# PCBMINI.net
KiCad netlist of a schematic drawn in EAGLE
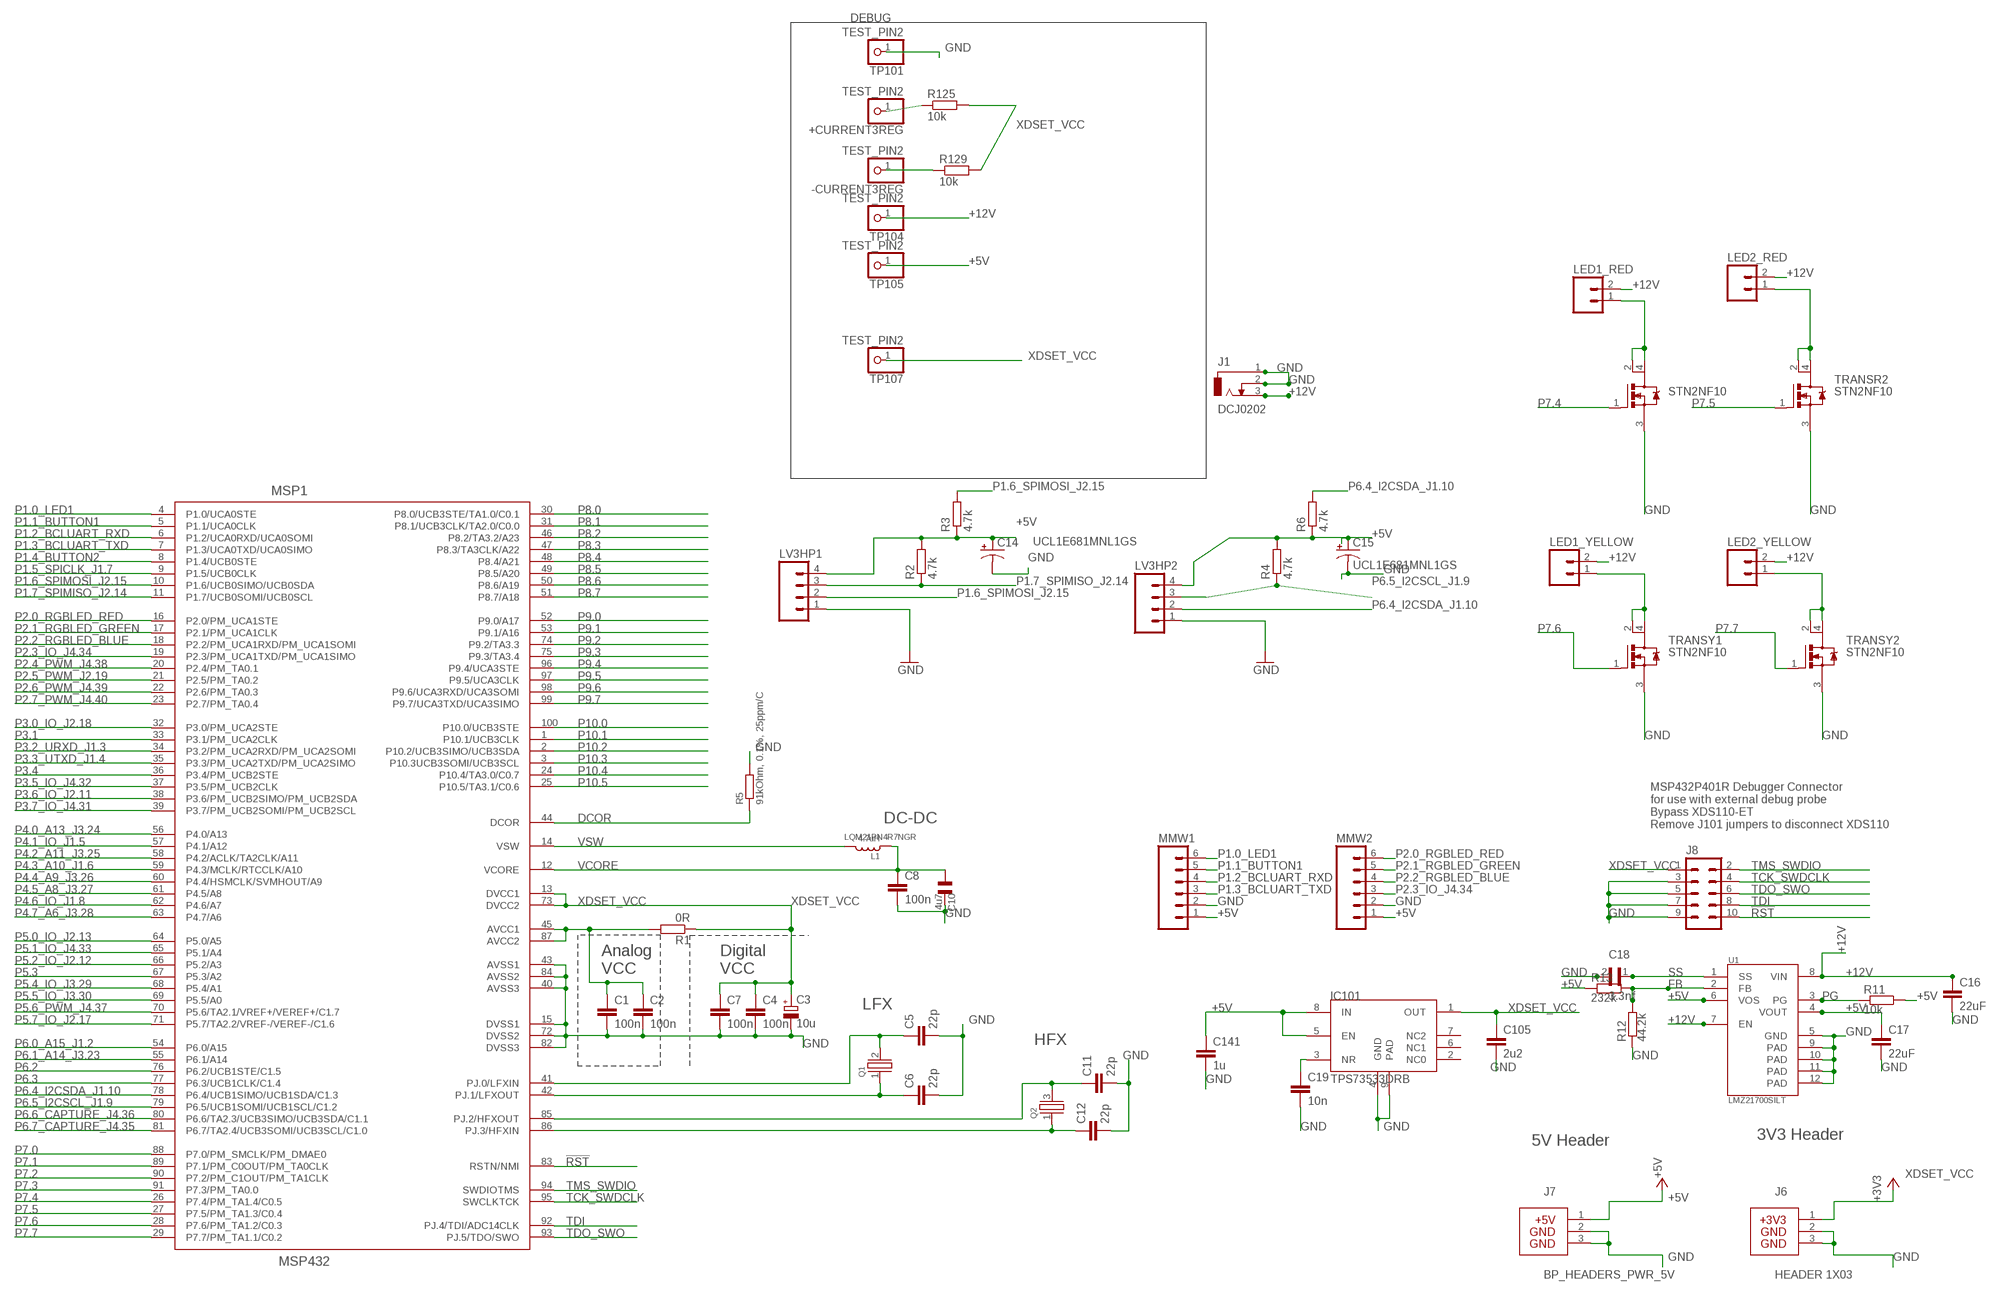
[diagram p0: schematic, sheet 1, part 1 of 2]
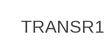
[diagram p1: schematic, sheet 1, part 2 of 2]

(export (version "E")
  (design (tool "Eeschema 10.0.6"))
  (components
    (comp (ref "+CURRENT3REG")
      (value "TEST_PIN2")
      (footprint "eagle-import:1X01")
      (libsource (lib "eagle-import") (part "PINHD-1X1"))
    )
    (comp (ref "-CURRENT3REG")
      (value "TEST_PIN2")
      (footprint "eagle-import:1X01")
      (libsource (lib "eagle-import") (part "PINHD-1X1"))
    )
    (comp (ref "C1")
      (value "100n")
      (footprint "eagle-import:0402")
      (libsource (lib "eagle-import") (part "C-EUCM0402"))
    )
    (comp (ref "C2")
      (value "100n")
      (footprint "eagle-import:0402")
      (libsource (lib "eagle-import") (part "C-EUCM0402"))
    )
    (comp (ref "C3")
      (value "10u")
      (footprint "eagle-import:A_3216-18R")
      (libsource (lib "eagle-import") (part "CPOL-EUA/3216-18R"))
    )
    (comp (ref "C4")
      (value "100n")
      (footprint "eagle-import:0402")
      (libsource (lib "eagle-import") (part "C-EUCM0402"))
    )
    (comp (ref "C5")
      (value "22p")
      (footprint "eagle-import:0402")
      (libsource (lib "eagle-import") (part "C-EUCM0402"))
    )
    (comp (ref "C6")
      (value "22p")
      (footprint "eagle-import:0402")
      (libsource (lib "eagle-import") (part "C-EUCM0402"))
    )
    (comp (ref "C7")
      (value "100n")
      (footprint "eagle-import:0402")
      (libsource (lib "eagle-import") (part "C-EUCM0402"))
    )
    (comp (ref "C8")
      (value "100n")
      (footprint "eagle-import:0402")
      (libsource (lib "eagle-import") (part "C-EUCM0402"))
    )
    (comp (ref "C10")
      (value "4u7")
      (footprint "eagle-import:CSMD0805")
      (libsource (lib "eagle-import") (part "CSMD0805"))
    )
    (comp (ref "C11")
      (value "22p")
      (footprint "eagle-import:0402")
      (libsource (lib "eagle-import") (part "C-EUCM0402"))
    )
    (comp (ref "C12")
      (value "22p")
      (footprint "eagle-import:0402")
      (libsource (lib "eagle-import") (part "C-EUCM0402"))
    )
    (comp (ref "C14")
      (value "UCL1E681MNL1GS")
      (footprint "eagle-import:CAPAE1030X1350N")
      (fields (field (name "MF") "Nichicon"))
      (libsource (lib "eagle-import") (part "UCL1E681MNL1GS"))
    )
    (comp (ref "C15")
      (value "UCL1E681MNL1GS")
      (footprint "eagle-import:CAPAE1030X1350N")
      (fields (field (name "MF") "Nichicon"))
      (libsource (lib "eagle-import") (part "UCL1E681MNL1GS"))
    )
    (comp (ref "C16")
      (value "22uF")
      (footprint "eagle-import:0805")
      (libsource (lib "eagle-import") (part "22UF-0805-6.3V-20%"))
    )
    (comp (ref "C17")
      (value "22uF")
      (footprint "eagle-import:0805")
      (libsource (lib "eagle-import") (part "22UF-0805-6.3V-20%"))
    )
    (comp (ref "C18")
      (value "3.3nf")
      (footprint "eagle-import:CAPC1005X55N")
      (fields (field (name "MF") "KEMET") (field (name "MP") "C0402C332K5RACTU"))
      (libsource (lib "eagle-import") (part "C0402C332K5RACTU"))
    )
    (comp (ref "C19")
      (value "10n")
      (footprint "eagle-import:C0603")
      (libsource (lib "eagle-import") (part "C-EUC0603"))
    )
    (comp (ref "C105")
      (value "2u2")
      (footprint "eagle-import:C0603")
      (libsource (lib "eagle-import") (part "C-EUC0603"))
    )
    (comp (ref "C141")
      (value "1u")
      (footprint "eagle-import:C0603")
      (libsource (lib "eagle-import") (part "C-EUC0603"))
    )
    (comp (ref "IC101")
      (value "TPS73533DRB")
      (footprint "eagle-import:SON8")
      (libsource (lib "eagle-import") (part "TPS73633DRB"))
    )
    (comp (ref "J1")
      (value "DCJ0202")
      (footprint "eagle-import:DCJ0202")
      (libsource (lib "eagle-import") (part "DCJ0202"))
    )
    (comp (ref "J6")
      (value "HEADER 1X03")
      (footprint "eagle-import:3PIN_PWR_3V3")
      (libsource (lib "eagle-import") (part "BP_HEADERS_PWR_3V3-TH100"))
    )
    (comp (ref "J7")
      (value "BP_HEADERS_PWR_5V")
      (footprint "eagle-import:3PIN_PWR_5V")
      (libsource (lib "eagle-import") (part "BP_HEADERS_PWR_5V"))
    )
    (comp (ref "J8")
      (value "DEBUG_ARM-10")
      (footprint "eagle-import:ARM-10")
      (libsource (lib "eagle-import") (part "DEBUG_ARM-10"))
    )
    (comp (ref "L1")
      (value "4.7uH")
      (footprint "eagle-import:0806")
      (libsource (lib "eagle-import") (part "LQM2MP_G0"))
    )
    (comp (ref "LED1_RED")
      (value "MA02")
      (footprint "eagle-import:02PA")
      (libsource (lib "eagle-import") (part "MA02"))
    )
    (comp (ref "LED1_YELLOW")
      (value "MA02")
      (footprint "eagle-import:02PA")
      (libsource (lib "eagle-import") (part "MA02"))
    )
    (comp (ref "LED2_RED")
      (value "MA02")
      (footprint "eagle-import:02PA")
      (libsource (lib "eagle-import") (part "MA02"))
    )
    (comp (ref "LED2_YELLOW")
      (value "MA02")
      (footprint "eagle-import:02PA")
      (libsource (lib "eagle-import") (part "MA02"))
    )
    (comp (ref "LV3HP1")
      (value "MA04")
      (footprint "eagle-import:04PA")
      (libsource (lib "eagle-import") (part "MA04"))
    )
    (comp (ref "LV3HP2")
      (value "MA04")
      (footprint "eagle-import:04PA")
      (libsource (lib "eagle-import") (part "MA04"))
    )
    (comp (ref "MMW1")
      (value "MA06")
      (footprint "eagle-import:06PA")
      (libsource (lib "eagle-import") (part "MA06"))
    )
    (comp (ref "MMW2")
      (value "MA06")
      (footprint "eagle-import:06PA")
      (libsource (lib "eagle-import") (part "MA06"))
    )
    (comp (ref "MSP1")
      (value "MSP432")
      (footprint "eagle-import:PZ100")
      (libsource (lib "eagle-import") (part "MSP432"))
    )
    (comp (ref "Q1")
      (value "CRYSTALLF_GENERAL")
      (footprint "eagle-import:LF_XTAL")
      (libsource (lib "eagle-import") (part "CRYSTALLF_GENERAL"))
    )
    (comp (ref "Q2")
      (value "CRYSTALEPSON_FA-238")
      (footprint "eagle-import:FA-238")
      (libsource (lib "eagle-import") (part "CRYSTALEPSON_FA-238"))
    )
    (comp (ref "R1")
      (value "0R")
      (footprint "eagle-import:0402")
      (libsource (lib "eagle-import") (part "R-EU_RM0402"))
    )
    (comp (ref "R2")
      (value "4.7k")
      (footprint "eagle-import:0402")
      (libsource (lib "eagle-import") (part "R-EU_RM0402"))
    )
    (comp (ref "R3")
      (value "4.7k")
      (footprint "eagle-import:0402")
      (libsource (lib "eagle-import") (part "R-EU_RM0402"))
    )
    (comp (ref "R4")
      (value "4.7k")
      (footprint "eagle-import:0402")
      (libsource (lib "eagle-import") (part "R-EU_RM0402"))
    )
    (comp (ref "R5")
      (value "91kOhm, 0.1%, 25ppm/C")
      (footprint "eagle-import:0805")
      (libsource (lib "eagle-import") (part "R_0805"))
    )
    (comp (ref "R6")
      (value "4.7k")
      (footprint "eagle-import:0402")
      (libsource (lib "eagle-import") (part "R-EU_RM0402"))
    )
    (comp (ref "R11")
      (value "10k")
      (footprint "eagle-import:SMK")
      (libsource (lib "eagle-import") (part "SMK"))
    )
    (comp (ref "R12")
      (value "44.2k")
      (footprint "eagle-import:SMK")
      (libsource (lib "eagle-import") (part "SMK"))
    )
    (comp (ref "R13")
      (value "232k")
      (footprint "eagle-import:SMK")
      (libsource (lib "eagle-import") (part "SMK"))
    )
    (comp (ref "R125")
      (value "10k")
      (footprint "eagle-import:0402")
      (libsource (lib "eagle-import") (part "R-EU_RM0402"))
    )
    (comp (ref "R129")
      (value "10k")
      (footprint "eagle-import:0402")
      (libsource (lib "eagle-import") (part "R-EU_RM0402"))
    )
    (comp (ref "TP101")
      (value "TEST_PIN2")
      (footprint "eagle-import:1X01")
      (libsource (lib "eagle-import") (part "PINHD-1X1"))
    )
    (comp (ref "TP104")
      (value "TEST_PIN2")
      (footprint "eagle-import:1X01")
      (libsource (lib "eagle-import") (part "PINHD-1X1"))
    )
    (comp (ref "TP105")
      (value "TEST_PIN2")
      (footprint "eagle-import:1X01")
      (libsource (lib "eagle-import") (part "PINHD-1X1"))
    )
    (comp (ref "TP107")
      (value "TEST_PIN2")
      (footprint "eagle-import:1X01")
      (libsource (lib "eagle-import") (part "PINHD-1X1"))
    )
    (comp (ref "TRANSR1")
      (value "STN2NF10")
      (footprint "eagle-import:SOT230P700X180-4N")
      (fields (field (name "MF") "STMicroelectronics"))
      (libsource (lib "eagle-import") (part "STN2NF10"))
    )
    (comp (ref "TRANSR2")
      (value "STN2NF10")
      (footprint "eagle-import:SOT230P700X180-4N")
      (fields (field (name "MF") "STMicroelectronics"))
      (libsource (lib "eagle-import") (part "STN2NF10"))
    )
    (comp (ref "TRANSY1")
      (value "STN2NF10")
      (footprint "eagle-import:SOT230P700X180-4N")
      (fields (field (name "MF") "STMicroelectronics"))
      (libsource (lib "eagle-import") (part "STN2NF10"))
    )
    (comp (ref "TRANSY2")
      (value "STN2NF10")
      (footprint "eagle-import:SOT230P700X180-4N")
      (fields (field (name "MF") "STMicroelectronics"))
      (libsource (lib "eagle-import") (part "STN2NF10"))
    )
    (comp (ref "U1")
      (value "LMZ21700SILT")
      (footprint "eagle-import:DFN350X350X175-10RN")
      (fields (field (name "MF") "Texas Instruments"))
      (libsource (lib "eagle-import") (part "LMZ21700SILT"))
    )
  )
  (nets
    (net (code "1") (name "+3V3") (class "Default")
      (node (ref "C105") (pin "1") (pinfunction "1_1") (pintype "passive"))
      (node (ref "C3") (pin "+") (pinfunction "+_+") (pintype "passive"))
      (node (ref "C4") (pin "1") (pinfunction "1_1") (pintype "passive"))
      (node (ref "C7") (pin "1") (pinfunction "1_1") (pintype "passive"))
      (node (ref "IC101") (pin "1") (pinfunction "OUT_1") (pintype "bidirectional"))
      (node (ref "J6") (pin "1") (pinfunction "1_1") (pintype "bidirectional"))
      (node (ref "J8") (pin "1") (pinfunction "1_1") (pintype "passive"))
      (node (ref "MSP1") (pin "13") (pinfunction "DVCC1_13") (pintype "power_in"))
      (node (ref "MSP1") (pin "73") (pinfunction "DVCC2_73") (pintype "power_in"))
      (node (ref "R1") (pin "1") (pinfunction "1_1") (pintype "passive"))
      (node (ref "R125") (pin "2") (pinfunction "2_2") (pintype "passive"))
      (node (ref "R129") (pin "2") (pinfunction "2_2") (pintype "passive"))
      (node (ref "TP107") (pin "1") (pinfunction "1_1") (pintype "passive"))
    )
    (net (code "2") (name "+5V") (class "Default")
      (node (ref "C14") (pin "A") (pinfunction "+_A") (pintype "passive"))
      (node (ref "C141") (pin "1") (pinfunction "1_1") (pintype "passive"))
      (node (ref "C15") (pin "A") (pinfunction "+_A") (pintype "passive"))
      (node (ref "C17") (pin "1") (pinfunction "1_1") (pintype "passive"))
      (node (ref "IC101") (pin "5") (pinfunction "EN_5") (pintype "bidirectional"))
      (node (ref "IC101") (pin "8") (pinfunction "IN_8") (pintype "bidirectional"))
      (node (ref "J7") (pin "1") (pinfunction "1_1") (pintype "bidirectional"))
      (node (ref "LV3HP1") (pin "4") (pinfunction "4_4") (pintype "passive"))
      (node (ref "LV3HP2") (pin "4") (pinfunction "4_4") (pintype "passive"))
      (node (ref "MMW1") (pin "1") (pinfunction "1_1") (pintype "passive"))
      (node (ref "MMW2") (pin "1") (pinfunction "1_1") (pintype "passive"))
      (node (ref "R11") (pin "1") (pinfunction "1_1") (pintype "passive"))
      (node (ref "R13") (pin "2") (pinfunction "2_2") (pintype "passive"))
      (node (ref "R2") (pin "2") (pinfunction "2_2") (pintype "passive"))
      (node (ref "R3") (pin "1") (pinfunction "1_1") (pintype "passive"))
      (node (ref "R4") (pin "2") (pinfunction "2_2") (pintype "passive"))
      (node (ref "R6") (pin "1") (pinfunction "1_1") (pintype "passive"))
      (node (ref "TP105") (pin "1") (pinfunction "1_1") (pintype "passive"))
      (node (ref "U1") (pin "4") (pinfunction "VOUT_4") (pintype "output"))
      (node (ref "U1") (pin "6") (pinfunction "VOS_6") (pintype "input"))
    )
    (net (code "3") (name "/+12V") (class "Default")
      (node (ref "C16") (pin "1") (pinfunction "1_1") (pintype "passive"))
      (node (ref "J1") (pin "3") (pinfunction "3_3") (pintype "passive"))
      (node (ref "LED1_RED") (pin "2") (pinfunction "2_2") (pintype "passive"))
      (node (ref "LED1_YELLOW") (pin "2") (pinfunction "2_2") (pintype "passive"))
      (node (ref "LED2_RED") (pin "2") (pinfunction "2_2") (pintype "passive"))
      (node (ref "LED2_YELLOW") (pin "2") (pinfunction "2_2") (pintype "passive"))
      (node (ref "TP104") (pin "1") (pinfunction "1_1") (pintype "passive"))
      (node (ref "U1") (pin "7") (pinfunction "EN_7") (pintype "input"))
      (node (ref "U1") (pin "8") (pinfunction "VIN_8") (pintype "power_in"))
    )
    (net (code "4") (name "/DCOR") (class "Default")
      (node (ref "MSP1") (pin "44") (pinfunction "DCOR_44") (pintype "power_in"))
      (node (ref "R5") (pin "1") (pinfunction "1_1") (pintype "passive"))
    )
    (net (code "5") (name "/FB") (class "Default")
      (node (ref "R12") (pin "1") (pinfunction "1_1") (pintype "passive"))
      (node (ref "R13") (pin "1") (pinfunction "1_1") (pintype "passive"))
      (node (ref "U1") (pin "2") (pinfunction "FB_2") (pintype "input"))
    )
    (net (code "6") (name "/P1.0_LED1") (class "Default")
      (node (ref "MMW1") (pin "6") (pinfunction "6_6") (pintype "passive"))
      (node (ref "MSP1") (pin "4") (pinfunction "P1.0/UCA0STE_4") (pintype "power_in"))
    )
    (net (code "7") (name "/P1.1_BUTTON1") (class "Default")
      (node (ref "MMW1") (pin "5") (pinfunction "5_5") (pintype "passive"))
      (node (ref "MSP1") (pin "5") (pinfunction "P1.1/UCA0CLK_5") (pintype "power_in"))
    )
    (net (code "8") (name "/P1.2_BCLUART_RXD") (class "Default")
      (node (ref "MMW1") (pin "4") (pinfunction "4_4") (pintype "passive"))
      (node (ref "MSP1") (pin "6") (pinfunction "P1.2/UCA0RXD/UCA0SOMI_6") (pintype "power_in"))
    )
    (net (code "9") (name "/P1.3_BCLUART_TXD") (class "Default")
      (node (ref "MMW1") (pin "3") (pinfunction "3_3") (pintype "passive"))
      (node (ref "MSP1") (pin "7") (pinfunction "P1.3/UCA0TXD/UCA0SIMO_7") (pintype "power_in"))
    )
    (net (code "10") (name "/P1.4_BUTTON2") (class "Default")
      (node (ref "MSP1") (pin "8") (pinfunction "P1.4/UCB0STE_8") (pintype "power_in"))
    )
    (net (code "11") (name "/P1.5_SPICLK_J1.7") (class "Default")
      (node (ref "MSP1") (pin "9") (pinfunction "P1.5/UCB0CLK_9") (pintype "power_in"))
    )
    (net (code "12") (name "/P1.6_SPIMOSI_J2.15") (class "Default")
      (node (ref "LV3HP1") (pin "2") (pinfunction "2_2") (pintype "passive"))
      (node (ref "MSP1") (pin "10") (pinfunction "P1.6/UCB0SIMO/UCB0SDA_10") (pintype "power_in"))
      (node (ref "R3") (pin "2") (pinfunction "2_2") (pintype "passive"))
    )
    (net (code "13") (name "/P1.7_SPIMISO_J2.14") (class "Default")
      (node (ref "LV3HP1") (pin "3") (pinfunction "3_3") (pintype "passive"))
      (node (ref "MSP1") (pin "11") (pinfunction "P1.7/UCB0SOMI/UCB0SCL_11") (pintype "power_in"))
      (node (ref "R2") (pin "1") (pinfunction "1_1") (pintype "passive"))
    )
    (net (code "14") (name "/P2.0_RGBLED_RED") (class "Default")
      (node (ref "MMW2") (pin "6") (pinfunction "6_6") (pintype "passive"))
      (node (ref "MSP1") (pin "16") (pinfunction "P2.0/PM_UCA1STE_16") (pintype "power_in"))
    )
    (net (code "15") (name "/P2.1_RGBLED_GREEN") (class "Default")
      (node (ref "MMW2") (pin "5") (pinfunction "5_5") (pintype "passive"))
      (node (ref "MSP1") (pin "17") (pinfunction "P2.1/PM_UCA1CLK_17") (pintype "power_in"))
    )
    (net (code "16") (name "/P2.2_RGBLED_BLUE") (class "Default")
      (node (ref "MMW2") (pin "4") (pinfunction "4_4") (pintype "passive"))
      (node (ref "MSP1") (pin "18") (pinfunction "P2.2/PM_UCA1RXD/PM_UCA1SOMI_18") (pintype "power_in"))
    )
    (net (code "17") (name "/P2.3_IO_J4.34") (class "Default")
      (node (ref "MMW2") (pin "3") (pinfunction "3_3") (pintype "passive"))
      (node (ref "MSP1") (pin "19") (pinfunction "P2.3/PM_UCA1TXD/PM_UCA1SIMO_19") (pintype "power_in"))
    )
    (net (code "18") (name "/P2.4_PWM_J4.38") (class "Default")
      (node (ref "MSP1") (pin "20") (pinfunction "P2.4/PM_TA0.1_20") (pintype "power_in"))
    )
    (net (code "19") (name "/P2.5_PWM_J2.19") (class "Default")
      (node (ref "MSP1") (pin "21") (pinfunction "P2.5/PM_TA0.2_21") (pintype "power_in"))
    )
    (net (code "20") (name "/P2.6_PWM_J4.39") (class "Default")
      (node (ref "MSP1") (pin "22") (pinfunction "P2.6/PM_TA0.3_22") (pintype "power_in"))
    )
    (net (code "21") (name "/P2.7_PWM_J4.40") (class "Default")
      (node (ref "MSP1") (pin "23") (pinfunction "P2.7/PM_TA0.4_23") (pintype "power_in"))
    )
    (net (code "22") (name "/P3.0_IO_J2.18") (class "Default")
      (node (ref "MSP1") (pin "32") (pinfunction "P3.0/PM_UCA2STE_32") (pintype "power_in"))
    )
    (net (code "23") (name "/P3.1") (class "Default")
      (node (ref "MSP1") (pin "33") (pinfunction "P3.1/PM_UCA2CLK_33") (pintype "power_in"))
    )
    (net (code "24") (name "/P3.2_URXD_J1.3") (class "Default")
      (node (ref "MSP1") (pin "34") (pinfunction "P3.2/PM_UCA2RXD/PM_UCA2SOMI_34") (pintype "power_in"))
    )
    (net (code "25") (name "/P3.3_UTXD_J1.4") (class "Default")
      (node (ref "MSP1") (pin "35") (pinfunction "P3.3/PM_UCA2TXD/PM_UCA2SIMO_35") (pintype "power_in"))
    )
    (net (code "26") (name "/P3.4") (class "Default")
      (node (ref "MSP1") (pin "36") (pinfunction "P3.4/PM_UCB2STE_36") (pintype "power_in"))
    )
    (net (code "27") (name "/P3.5_IO_J4.32") (class "Default")
      (node (ref "MSP1") (pin "37") (pinfunction "P3.5/PM_UCB2CLK_37") (pintype "power_in"))
    )
    (net (code "28") (name "/P3.6_IO_J2.11") (class "Default")
      (node (ref "MSP1") (pin "38") (pinfunction "P3.6/PM_UCB2SIMO/PM_UCB2SDA_38") (pintype "power_in"))
    )
    (net (code "29") (name "/P3.7_IO_J4.31") (class "Default")
      (node (ref "MSP1") (pin "39") (pinfunction "P3.7/PM_UCB2SOMI/PM_UCB2SCL_39") (pintype "power_in"))
    )
    (net (code "30") (name "/P4.0_A13_J3.24") (class "Default")
      (node (ref "MSP1") (pin "56") (pinfunction "P4.0/A13_56") (pintype "power_in"))
    )
    (net (code "31") (name "/P4.1_IO_J1.5") (class "Default")
      (node (ref "MSP1") (pin "57") (pinfunction "P4.1/A12_57") (pintype "power_in"))
    )
    (net (code "32") (name "/P4.2_A11_J3.25") (class "Default")
      (node (ref "MSP1") (pin "58") (pinfunction "P4.2/ACLK/TA2CLK/A11_58") (pintype "power_in"))
    )
    (net (code "33") (name "/P4.3_A10_J1.6") (class "Default")
      (node (ref "MSP1") (pin "59") (pinfunction "P4.3/MCLK/RTCCLK/A10_59") (pintype "power_in"))
    )
    (net (code "34") (name "/P4.4_A9_J3.26") (class "Default")
      (node (ref "MSP1") (pin "60") (pinfunction "P4.4/HSMCLK/SVMHOUT/A9_60") (pintype "power_in"))
    )
    (net (code "35") (name "/P4.5_A8_J3.27") (class "Default")
      (node (ref "MSP1") (pin "61") (pinfunction "P4.5/A8_61") (pintype "power_in"))
    )
    (net (code "36") (name "/P4.6_IO_J1.8") (class "Default")
      (node (ref "MSP1") (pin "62") (pinfunction "P4.6/A7_62") (pintype "power_in"))
    )
    (net (code "37") (name "/P4.7_A6_J3.28") (class "Default")
      (node (ref "MSP1") (pin "63") (pinfunction "P4.7/A6_63") (pintype "power_in"))
    )
    (net (code "38") (name "/P5.0_IO_J2.13") (class "Default")
      (node (ref "MSP1") (pin "64") (pinfunction "P5.0/A5_64") (pintype "power_in"))
    )
    (net (code "39") (name "/P5.1_IO_J4.33") (class "Default")
      (node (ref "MSP1") (pin "65") (pinfunction "P5.1/A4_65") (pintype "power_in"))
    )
    (net (code "40") (name "/P5.2_IO_J2.12") (class "Default")
      (node (ref "MSP1") (pin "66") (pinfunction "P5.2/A3_66") (pintype "power_in"))
    )
    (net (code "41") (name "/P5.3") (class "Default")
      (node (ref "MSP1") (pin "67") (pinfunction "P5.3/A2_67") (pintype "power_in"))
    )
    (net (code "42") (name "/P5.4_IO_J3.29") (class "Default")
      (node (ref "MSP1") (pin "68") (pinfunction "P5.4/A1_68") (pintype "power_in"))
    )
    (net (code "43") (name "/P5.5_IO_J3.30") (class "Default")
      (node (ref "MSP1") (pin "69") (pinfunction "P5.5/A0_69") (pintype "power_in"))
    )
    (net (code "44") (name "/P5.6_PWM_J4.37") (class "Default")
      (node (ref "MSP1") (pin "70") (pinfunction "P5.6/TA2.1/VREF+/VEREF+/C1.7_70") (pintype "power_in"))
    )
    (net (code "45") (name "/P5.7_IO_J2.17") (class "Default")
      (node (ref "MSP1") (pin "71") (pinfunction "P5.7/TA2.2/VREF-/VEREF-/C1.6_71") (pintype "power_in"))
    )
    (net (code "46") (name "/P6.0_A15_J1.2") (class "Default")
      (node (ref "MSP1") (pin "54") (pinfunction "P6.0/A15_54") (pintype "power_in"))
    )
    (net (code "47") (name "/P6.1_A14_J3.23") (class "Default")
      (node (ref "MSP1") (pin "55") (pinfunction "P6.1/A14_55") (pintype "power_in"))
    )
    (net (code "48") (name "/P6.2") (class "Default")
      (node (ref "MSP1") (pin "76") (pinfunction "P6.2/UCB1STE/C1.5_76") (pintype "power_in"))
    )
    (net (code "49") (name "/P6.3") (class "Default")
      (node (ref "MSP1") (pin "77") (pinfunction "P6.3/UCB1CLK/C1.4_77") (pintype "power_in"))
    )
    (net (code "50") (name "/P6.4_I2CSDA_J1.10") (class "Default")
      (node (ref "LV3HP2") (pin "2") (pinfunction "2_2") (pintype "passive"))
      (node (ref "MSP1") (pin "78") (pinfunction "P6.4/UCB1SIMO/UCB1SDA/C1.3_78") (pintype "power_in"))
      (node (ref "R6") (pin "2") (pinfunction "2_2") (pintype "passive"))
    )
    (net (code "51") (name "/P6.5_I2CSCL_J1.9") (class "Default")
      (node (ref "LV3HP2") (pin "3") (pinfunction "3_3") (pintype "passive"))
      (node (ref "MSP1") (pin "79") (pinfunction "P6.5/UCB1SOMI/UCB1SCL/C1.2_79") (pintype "power_in"))
      (node (ref "R4") (pin "1") (pinfunction "1_1") (pintype "passive"))
    )
    (net (code "52") (name "/P6.6_CAPTURE_J4.36") (class "Default")
      (node (ref "MSP1") (pin "80") (pinfunction "P6.6/TA2.3/UCB3SIMO/UCB3SDA/C1.1_80") (pintype "power_in"))
    )
    (net (code "53") (name "/P6.7_CAPTURE_J4.35") (class "Default")
      (node (ref "MSP1") (pin "81") (pinfunction "P6.7/TA2.4/UCB3SOMI/UCB3SCL/C1.0_81") (pintype "power_in"))
    )
    (net (code "54") (name "/P7.0") (class "Default")
      (node (ref "MSP1") (pin "88") (pinfunction "P7.0/PM_SMCLK/PM_DMAE0_88") (pintype "power_in"))
    )
    (net (code "55") (name "/P7.1") (class "Default")
      (node (ref "MSP1") (pin "89") (pinfunction "P7.1/PM_C0OUT/PM_TA0CLK_89") (pintype "power_in"))
    )
    (net (code "56") (name "/P7.2") (class "Default")
      (node (ref "MSP1") (pin "90") (pinfunction "P7.2/PM_C1OUT/PM_TA1CLK_90") (pintype "power_in"))
    )
    (net (code "57") (name "/P7.3") (class "Default")
      (node (ref "MSP1") (pin "91") (pinfunction "P7.3/PM_TA0.0_91") (pintype "power_in"))
    )
    (net (code "58") (name "/P7.4") (class "Default")
      (node (ref "MSP1") (pin "26") (pinfunction "P7.4/PM_TA1.4/C0.5_26") (pintype "power_in"))
      (node (ref "TRANSR1") (pin "1") (pinfunction "G_1") (pintype "passive"))
    )
    (net (code "59") (name "/P7.5") (class "Default")
      (node (ref "MSP1") (pin "27") (pinfunction "P7.5/PM_TA1.3/C0.4_27") (pintype "power_in"))
      (node (ref "TRANSR2") (pin "1") (pinfunction "G_1") (pintype "passive"))
    )
    (net (code "60") (name "/P7.6") (class "Default")
      (node (ref "MSP1") (pin "28") (pinfunction "P7.6/PM_TA1.2/C0.3_28") (pintype "power_in"))
      (node (ref "TRANSY1") (pin "1") (pinfunction "G_1") (pintype "passive"))
    )
    (net (code "61") (name "/P7.7") (class "Default")
      (node (ref "MSP1") (pin "29") (pinfunction "P7.7/PM_TA1.1/C0.2_29") (pintype "power_in"))
      (node (ref "TRANSY2") (pin "1") (pinfunction "G_1") (pintype "passive"))
    )
    (net (code "62") (name "/P8.0") (class "Default")
      (node (ref "MSP1") (pin "30") (pinfunction "P8.0/UCB3STE/TA1.0/C0.1_30") (pintype "power_in"))
    )
    (net (code "63") (name "/P8.1") (class "Default")
      (node (ref "MSP1") (pin "31") (pinfunction "P8.1/UCB3CLK/TA2.0/C0.0_31") (pintype "power_in"))
    )
    (net (code "64") (name "/P8.2") (class "Default")
      (node (ref "MSP1") (pin "46") (pinfunction "P8.2/TA3.2/A23_46") (pintype "power_in"))
    )
    (net (code "65") (name "/P8.3") (class "Default")
      (node (ref "MSP1") (pin "47") (pinfunction "P8.3/TA3CLK/A22_47") (pintype "power_in"))
    )
    (net (code "66") (name "/P8.4") (class "Default")
      (node (ref "MSP1") (pin "48") (pinfunction "P8.4/A21_48") (pintype "power_in"))
    )
    (net (code "67") (name "/P8.5") (class "Default")
      (node (ref "MSP1") (pin "49") (pinfunction "P8.5/A20_49") (pintype "power_in"))
    )
    (net (code "68") (name "/P8.6") (class "Default")
      (node (ref "MSP1") (pin "50") (pinfunction "P8.6/A19_50") (pintype "power_in"))
    )
    (net (code "69") (name "/P8.7") (class "Default")
      (node (ref "MSP1") (pin "51") (pinfunction "P8.7/A18_51") (pintype "power_in"))
    )
    (net (code "70") (name "/P9.0") (class "Default")
      (node (ref "MSP1") (pin "52") (pinfunction "P9.0/A17_52") (pintype "power_in"))
    )
    (net (code "71") (name "/P9.1") (class "Default")
      (node (ref "MSP1") (pin "53") (pinfunction "P9.1/A16_53") (pintype "power_in"))
    )
    (net (code "72") (name "/P9.2") (class "Default")
      (node (ref "MSP1") (pin "74") (pinfunction "P9.2/TA3.3_74") (pintype "power_in"))
    )
    (net (code "73") (name "/P9.3") (class "Default")
      (node (ref "MSP1") (pin "75") (pinfunction "P9.3/TA3.4_75") (pintype "power_in"))
    )
    (net (code "74") (name "/P9.4") (class "Default")
      (node (ref "MSP1") (pin "96") (pinfunction "P9.4/UCA3STE_96") (pintype "power_in"))
    )
    (net (code "75") (name "/P9.5") (class "Default")
      (node (ref "MSP1") (pin "97") (pinfunction "P9.5/UCA3CLK_97") (pintype "power_in"))
    )
    (net (code "76") (name "/P9.6") (class "Default")
      (node (ref "MSP1") (pin "98") (pinfunction "P9.6/UCA3RXD/UCA3SOMI_98") (pintype "power_in"))
    )
    (net (code "77") (name "/P9.7") (class "Default")
      (node (ref "MSP1") (pin "99") (pinfunction "P9.7/UCA3TXD/UCA3SIMO_99") (pintype "power_in"))
    )
    (net (code "78") (name "/P10.0") (class "Default")
      (node (ref "MSP1") (pin "100") (pinfunction "P10.0/UCB3STE_100") (pintype "power_in"))
    )
    (net (code "79") (name "/P10.1") (class "Default")
      (node (ref "MSP1") (pin "1") (pinfunction "P10.1/UCB3CLK_1") (pintype "power_in"))
    )
    (net (code "80") (name "/P10.2") (class "Default")
      (node (ref "MSP1") (pin "2") (pinfunction "P10.2/UCB3SIMO/UCB3SDA_2") (pintype "power_in"))
    )
    (net (code "81") (name "/P10.3") (class "Default")
      (node (ref "MSP1") (pin "3") (pinfunction "P10.3UCB3SOMI/UCB3SCL_3") (pintype "power_in"))
    )
    (net (code "82") (name "/P10.4") (class "Default")
      (node (ref "MSP1") (pin "24") (pinfunction "P10.4/TA3.0/C0.7_24") (pintype "power_in"))
    )
    (net (code "83") (name "/P10.5") (class "Default")
      (node (ref "MSP1") (pin "25") (pinfunction "P10.5/TA3.1/C0.6_25") (pintype "power_in"))
    )
    (net (code "84") (name "/PG") (class "Default")
      (node (ref "R11") (pin "2") (pinfunction "2_2") (pintype "passive"))
      (node (ref "U1") (pin "3") (pinfunction "PG_3") (pintype "output"))
    )
    (net (code "85") (name "/SS") (class "Default")
      (node (ref "C18") (pin "1") (pinfunction "1_1") (pintype "passive"))
      (node (ref "U1") (pin "1") (pinfunction "SS_1") (pintype "input"))
    )
    (net (code "86") (name "/TCK_SWDCLK") (class "Default")
      (node (ref "J8") (pin "4") (pinfunction "4_4") (pintype "passive"))
      (node (ref "MSP1") (pin "95") (pinfunction "SWCLKTCK_95") (pintype "power_in"))
    )
    (net (code "87") (name "/TDI") (class "Default")
      (node (ref "J8") (pin "8") (pinfunction "8_8") (pintype "passive"))
      (node (ref "MSP1") (pin "92") (pinfunction "PJ.4/TDI/ADC14CLK_92") (pintype "power_in"))
    )
    (net (code "88") (name "/TDO_SWO") (class "Default")
      (node (ref "J8") (pin "6") (pinfunction "6_6") (pintype "passive"))
      (node (ref "MSP1") (pin "93") (pinfunction "PJ.5/TDO/SWO_93") (pintype "power_in"))
    )
    (net (code "89") (name "/TMS_SWDIO") (class "Default")
      (node (ref "J8") (pin "2") (pinfunction "2_2") (pintype "passive"))
      (node (ref "MSP1") (pin "94") (pinfunction "SWDIOTMS_94") (pintype "power_in"))
    )
    (net (code "90") (name "/VCORE") (class "Default")
      (node (ref "C10") (pin "1") (pinfunction "1_1") (pintype "passive"))
      (node (ref "C8") (pin "1") (pinfunction "1_1") (pintype "passive"))
      (node (ref "L1") (pin "1") (pinfunction "1_1") (pintype "passive"))
      (node (ref "MSP1") (pin "12") (pinfunction "VCORE_12") (pintype "power_in"))
    )
    (net (code "91") (name "/VSW") (class "Default")
      (node (ref "L1") (pin "2") (pinfunction "2_2") (pintype "passive"))
      (node (ref "MSP1") (pin "14") (pinfunction "VSW_14") (pintype "power_in"))
    )
    (net (code "92") (name "/~{RST}") (class "Default")
      (node (ref "J8") (pin "10") (pinfunction "10_10") (pintype "passive"))
      (node (ref "MSP1") (pin "83") (pinfunction "RSTN/NMI_83") (pintype "power_in"))
    )
    (net (code "93") (name "GND") (class "Default")
      (node (ref "C1") (pin "2") (pinfunction "2_2") (pintype "passive"))
      (node (ref "C10") (pin "2") (pinfunction "2_2") (pintype "passive"))
      (node (ref "C105") (pin "2") (pinfunction "2_2") (pintype "passive"))
      (node (ref "C11") (pin "2") (pinfunction "2_2") (pintype "passive"))
      (node (ref "C12") (pin "2") (pinfunction "2_2") (pintype "passive"))
      (node (ref "C14") (pin "C") (pinfunction "-_C") (pintype "passive"))
      (node (ref "C141") (pin "2") (pinfunction "2_2") (pintype "passive"))
      (node (ref "C15") (pin "C") (pinfunction "-_C") (pintype "passive"))
      (node (ref "C16") (pin "2") (pinfunction "2_2") (pintype "passive"))
      (node (ref "C17") (pin "2") (pinfunction "2_2") (pintype "passive"))
      (node (ref "C18") (pin "2") (pinfunction "2_2") (pintype "passive"))
      (node (ref "C19") (pin "2") (pinfunction "2_2") (pintype "passive"))
      (node (ref "C2") (pin "2") (pinfunction "2_2") (pintype "passive"))
      (node (ref "C3") (pin "-") (pinfunction "-_-") (pintype "passive"))
      (node (ref "C4") (pin "2") (pinfunction "2_2") (pintype "passive"))
      (node (ref "C5") (pin "2") (pinfunction "2_2") (pintype "passive"))
      (node (ref "C6") (pin "2") (pinfunction "2_2") (pintype "passive"))
      (node (ref "C7") (pin "2") (pinfunction "2_2") (pintype "passive"))
      (node (ref "C8") (pin "2") (pinfunction "2_2") (pintype "passive"))
      (node (ref "IC101") (pin "4") (pinfunction "GND_4") (pintype "bidirectional"))
      (node (ref "IC101") (pin "9") (pinfunction "PAD_9") (pintype "bidirectional"))
      (node (ref "J1") (pin "1") (pinfunction "1_1") (pintype "passive"))
      (node (ref "J1") (pin "2") (pinfunction "2_2") (pintype "passive"))
      (node (ref "J6") (pin "2") (pinfunction "2_2") (pintype "bidirectional"))
      (node (ref "J6") (pin "3") (pinfunction "3_3") (pintype "bidirectional"))
      (node (ref "J7") (pin "2") (pinfunction "2_2") (pintype "bidirectional"))
      (node (ref "J7") (pin "3") (pinfunction "3_3") (pintype "bidirectional"))
      (node (ref "J8") (pin "3") (pinfunction "3_3") (pintype "passive"))
      (node (ref "J8") (pin "5") (pinfunction "5_5") (pintype "passive"))
      (node (ref "J8") (pin "7") (pinfunction "7_7") (pintype "passive"))
      (node (ref "J8") (pin "9") (pinfunction "9_9") (pintype "passive"))
      (node (ref "LV3HP1") (pin "1") (pinfunction "1_1") (pintype "passive"))
      (node (ref "LV3HP2") (pin "1") (pinfunction "1_1") (pintype "passive"))
      (node (ref "MMW1") (pin "2") (pinfunction "2_2") (pintype "passive"))
      (node (ref "MMW2") (pin "2") (pinfunction "2_2") (pintype "passive"))
      (node (ref "MSP1") (pin "15") (pinfunction "DVSS1_15") (pintype "power_in"))
      (node (ref "MSP1") (pin "40") (pinfunction "AVSS3_40") (pintype "power_in"))
      (node (ref "MSP1") (pin "43") (pinfunction "AVSS1_43") (pintype "power_in"))
      (node (ref "MSP1") (pin "72") (pinfunction "DVSS2_72") (pintype "power_in"))
      (node (ref "MSP1") (pin "82") (pinfunction "DVSS3_82") (pintype "power_in"))
      (node (ref "MSP1") (pin "84") (pinfunction "AVSS2_84") (pintype "power_in"))
      (node (ref "R12") (pin "2") (pinfunction "2_2") (pintype "passive"))
      (node (ref "R5") (pin "2") (pinfunction "2_2") (pintype "passive"))
      (node (ref "TP101") (pin "1") (pinfunction "1_1") (pintype "passive"))
      (node (ref "TRANSR1") (pin "3") (pinfunction "S_3") (pintype "passive"))
      (node (ref "TRANSR2") (pin "3") (pinfunction "S_3") (pintype "passive"))
      (node (ref "TRANSY1") (pin "3") (pinfunction "S_3") (pintype "passive"))
      (node (ref "TRANSY2") (pin "3") (pinfunction "S_3") (pintype "passive"))
    )
    (net (code "94") (name "Net-(+CURRENT3REG-Pad1)") (class "Default")
      (node (ref "+CURRENT3REG") (pin "1") (pinfunction "1_1") (pintype "passive"))
      (node (ref "R125") (pin "1") (pinfunction "1_1") (pintype "passive"))
    )
    (net (code "95") (name "Net-(-CURRENT3REG-Pad1)") (class "Default")
      (node (ref "-CURRENT3REG") (pin "1") (pinfunction "1_1") (pintype "passive"))
      (node (ref "R129") (pin "1") (pinfunction "1_1") (pintype "passive"))
    )
    (net (code "96") (name "Net-(IC101-NR)") (class "Default")
      (node (ref "C19") (pin "1") (pinfunction "1_1") (pintype "passive"))
      (node (ref "IC101") (pin "3") (pinfunction "NR_3") (pintype "bidirectional"))
    )
    (net (code "97") (name "Net-(LED1_RED-Pad1)") (class "Default")
      (node (ref "LED1_RED") (pin "1") (pinfunction "1_1") (pintype "passive"))
      (node (ref "TRANSR1") (pin "2") (pinfunction "D_2") (pintype "passive"))
      (node (ref "TRANSR1") (pin "4") (pinfunction "D_4") (pintype "passive"))
    )
    (net (code "98") (name "Net-(LED1_YELLOW-Pad1)") (class "Default")
      (node (ref "LED1_YELLOW") (pin "1") (pinfunction "1_1") (pintype "passive"))
      (node (ref "TRANSY1") (pin "2") (pinfunction "D_2") (pintype "passive"))
      (node (ref "TRANSY1") (pin "4") (pinfunction "D_4") (pintype "passive"))
    )
    (net (code "99") (name "Net-(LED2_RED-Pad1)") (class "Default")
      (node (ref "LED2_RED") (pin "1") (pinfunction "1_1") (pintype "passive"))
      (node (ref "TRANSR2") (pin "2") (pinfunction "D_2") (pintype "passive"))
      (node (ref "TRANSR2") (pin "4") (pinfunction "D_4") (pintype "passive"))
    )
    (net (code "100") (name "Net-(LED2_YELLOW-Pad1)") (class "Default")
      (node (ref "LED2_YELLOW") (pin "1") (pinfunction "1_1") (pintype "passive"))
      (node (ref "TRANSY2") (pin "2") (pinfunction "D_2") (pintype "passive"))
      (node (ref "TRANSY2") (pin "4") (pinfunction "D_4") (pintype "passive"))
    )
    (net (code "101") (name "Net-(MSP1-AVCC1)") (class "Default")
      (node (ref "C1") (pin "1") (pinfunction "1_1") (pintype "passive"))
      (node (ref "C2") (pin "1") (pinfunction "1_1") (pintype "passive"))
      (node (ref "MSP1") (pin "45") (pinfunction "AVCC1_45") (pintype "power_in"))
      (node (ref "MSP1") (pin "87") (pinfunction "AVCC2_87") (pintype "power_in"))
      (node (ref "R1") (pin "2") (pinfunction "2_2") (pintype "passive"))
    )
    (net (code "102") (name "Net-(MSP1-PJ.0{slash}LFXIN)") (class "Default")
      (node (ref "C5") (pin "1") (pinfunction "1_1") (pintype "passive"))
      (node (ref "MSP1") (pin "41") (pinfunction "PJ.0/LFXIN_41") (pintype "power_in"))
      (node (ref "Q1") (pin "2") (pinfunction "2_2") (pintype "passive"))
    )
    (net (code "103") (name "Net-(MSP1-PJ.1{slash}LFXOUT)") (class "Default")
      (node (ref "C6") (pin "1") (pinfunction "1_1") (pintype "passive"))
      (node (ref "MSP1") (pin "42") (pinfunction "PJ.1/LFXOUT_42") (pintype "power_in"))
      (node (ref "Q1") (pin "1") (pinfunction "1_1") (pintype "passive"))
    )
    (net (code "104") (name "Net-(MSP1-PJ.2{slash}HFXOUT)") (class "Default")
      (node (ref "C11") (pin "1") (pinfunction "1_1") (pintype "passive"))
      (node (ref "MSP1") (pin "85") (pinfunction "PJ.2/HFXOUT_85") (pintype "power_in"))
      (node (ref "Q2") (pin "3") (pinfunction "2_3") (pintype "passive"))
    )
    (net (code "105") (name "Net-(MSP1-PJ.3{slash}HFXIN)") (class "Default")
      (node (ref "C12") (pin "1") (pinfunction "1_1") (pintype "passive"))
      (node (ref "MSP1") (pin "86") (pinfunction "PJ.3/HFXIN_86") (pintype "power_in"))
      (node (ref "Q2") (pin "1") (pinfunction "1_1") (pintype "passive"))
    )
    (net (code "106") (name "Net-(U1-GND)") (class "Default")
      (node (ref "U1") (pin "10") (pinfunction "PAD_10") (pintype "power_in"))
      (node (ref "U1") (pin "11") (pinfunction "PAD_11") (pintype "power_in"))
      (node (ref "U1") (pin "12") (pinfunction "PAD_12") (pintype "power_in"))
      (node (ref "U1") (pin "5") (pinfunction "GND_5") (pintype "power_in"))
      (node (ref "U1") (pin "9") (pinfunction "PAD_9") (pintype "power_in"))
    )
    (net (code "107") (name "unconnected-(IC101-NC0-Pad2)") (class "Default")
      (node (ref "IC101") (pin "2") (pinfunction "NC0_2") (pintype "bidirectional"))
    )
    (net (code "108") (name "unconnected-(IC101-NC1-Pad6)") (class "Default")
      (node (ref "IC101") (pin "6") (pinfunction "NC1_6") (pintype "bidirectional"))
    )
    (net (code "109") (name "unconnected-(IC101-NC2-Pad7)") (class "Default")
      (node (ref "IC101") (pin "7") (pinfunction "NC2_7") (pintype "bidirectional"))
    )
  )
)
